# layout.net
KiCad netlist of a schematic drawn in EAGLE
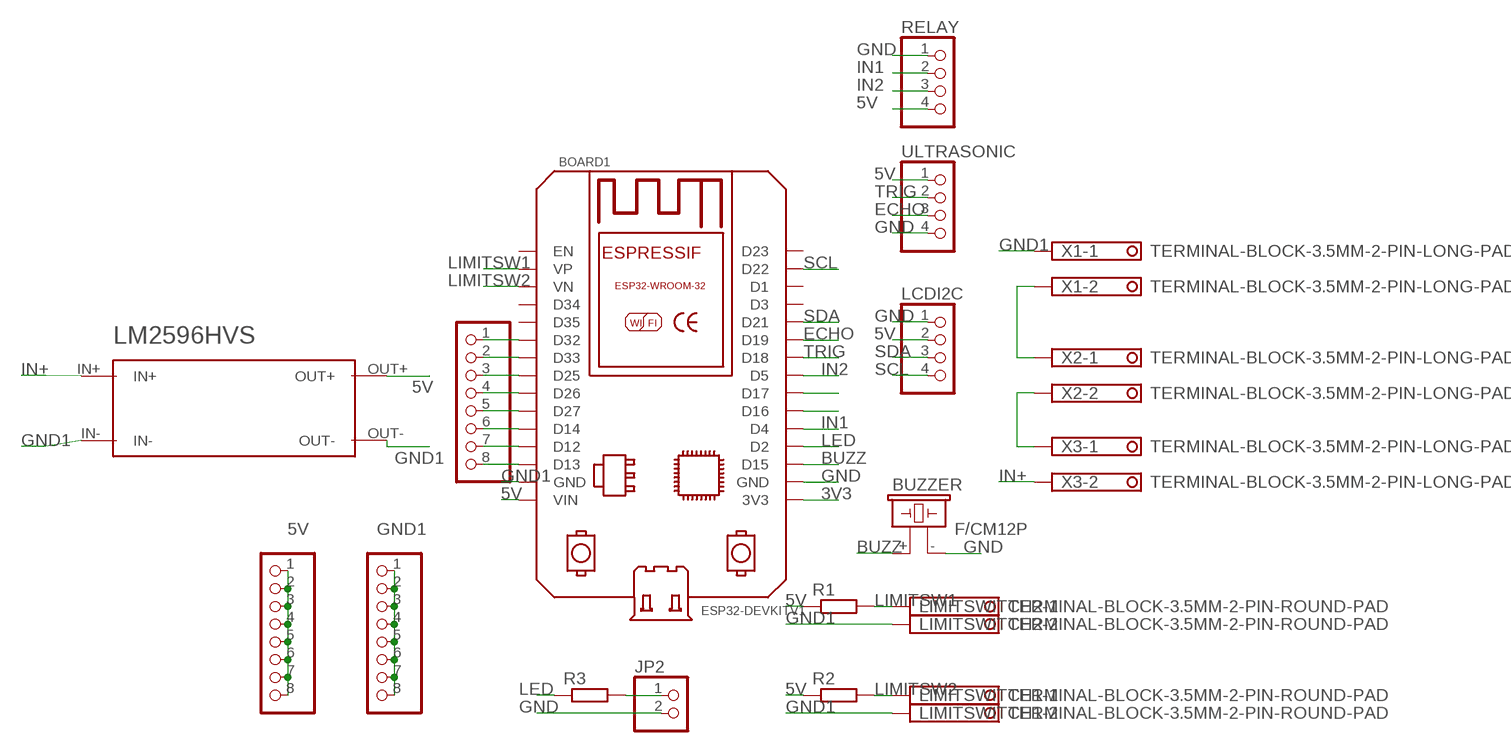
[diagram p0: schematic, sheet 1]

(export (version "E")
  (design (tool "Eeschema 10.0.6"))
  (components
    (comp (ref "BOARD1")
      (value "ESP32DEVKITV1SHRIDATTDUDHAT")
      (footprint "eagle-import:ESP32-DEVKITV1")
      (libsource (lib "eagle-import") (part "ESP32DEVKITV1SHRIDATTDUDHAT"))
    )
    (comp (ref "BUZZER")
      (value "F/CM12P")
      (footprint "eagle-import:F_CM12P")
      (libsource (lib "eagle-import") (part "F/CM12P"))
    )
    (comp (ref "JP1")
      (value "PINHD-1X8")
      (footprint "eagle-import:1X08")
      (libsource (lib "eagle-import") (part "PINHD-1X8"))
    )
    (comp (ref "JP2")
      (value "PINHD-1X2")
      (footprint "eagle-import:1X02")
      (libsource (lib "eagle-import") (part "PINHD-1X2"))
    )
    (comp (ref "JP3")
      (value "PINHD-1X8")
      (footprint "eagle-import:1X08")
      (libsource (lib "eagle-import") (part "PINHD-1X8"))
    )
    (comp (ref "JP4")
      (value "PINHD-1X8")
      (footprint "eagle-import:1X08")
      (libsource (lib "eagle-import") (part "PINHD-1X8"))
    )
    (comp (ref "LCDI2C")
      (value "PINHD-1X4")
      (footprint "eagle-import:1X04")
      (libsource (lib "eagle-import") (part "PINHD-1X4"))
    )
    (comp (ref "LIMITSWITCH1")
      (value "TERMINAL-BLOCK-3.5MM-2-PIN-ROUND-PAD")
      (footprint "eagle-import:TERMINAL-BLOCK-2-PIN-3.5MM-ROUND-PAD")
      (libsource (lib "eagle-import") (part "TERMINAL-BLOCK-3.5MM-2-PIN-ROUND-PAD"))
    )
    (comp (ref "LIMITSWITCH2")
      (value "TERMINAL-BLOCK-3.5MM-2-PIN-ROUND-PAD")
      (footprint "eagle-import:TERMINAL-BLOCK-2-PIN-3.5MM-ROUND-PAD")
      (libsource (lib "eagle-import") (part "TERMINAL-BLOCK-3.5MM-2-PIN-ROUND-PAD"))
    )
    (comp (ref "R1")
      (value "R-EU_0207/10")
      (footprint "eagle-import:0207_10")
      (libsource (lib "eagle-import") (part "R-EU_0207/10"))
    )
    (comp (ref "R2")
      (value "R-EU_0207/10")
      (footprint "eagle-import:0207_10")
      (libsource (lib "eagle-import") (part "R-EU_0207/10"))
    )
    (comp (ref "R3")
      (value "R-EU_0207/10")
      (footprint "eagle-import:0207_10")
      (libsource (lib "eagle-import") (part "R-EU_0207/10"))
    )
    (comp (ref "RELAY")
      (value "PINHD-1X4")
      (footprint "eagle-import:1X04")
      (libsource (lib "eagle-import") (part "PINHD-1X4"))
    )
    (comp (ref "STEP_DOWN1")
      (value "LM2596HVS")
      (footprint "eagle-import:LM2596HVS")
      (libsource (lib "eagle-import") (part "LM2596HVS"))
    )
    (comp (ref "ULTRASONIC")
      (value "PINHD-1X4")
      (footprint "eagle-import:1X04")
      (libsource (lib "eagle-import") (part "PINHD-1X4"))
    )
    (comp (ref "X1")
      (value "TERMINAL-BLOCK-3.5MM-2-PIN-LONG-PAD")
      (footprint "eagle-import:TERMINAL-BLOCK-2-PIN-3.5MM-LONG-PAD")
      (libsource (lib "eagle-import") (part "TERMINAL-BLOCK-3.5MM-2-PIN-LONG-PAD"))
    )
    (comp (ref "X2")
      (value "TERMINAL-BLOCK-3.5MM-2-PIN-LONG-PAD")
      (footprint "eagle-import:TERMINAL-BLOCK-2-PIN-3.5MM-LONG-PAD")
      (libsource (lib "eagle-import") (part "TERMINAL-BLOCK-3.5MM-2-PIN-LONG-PAD"))
    )
    (comp (ref "X3")
      (value "TERMINAL-BLOCK-3.5MM-2-PIN-LONG-PAD")
      (footprint "eagle-import:TERMINAL-BLOCK-2-PIN-3.5MM-LONG-PAD")
      (libsource (lib "eagle-import") (part "TERMINAL-BLOCK-3.5MM-2-PIN-LONG-PAD"))
    )
  )
  (nets
    (net (code "1") (name "/3V3") (class "Default")
      (node (ref "BOARD1") (pin "3V3") (pinfunction "3V3_3V3") (pintype "bidirectional"))
    )
    (net (code "2") (name "/5V") (class "Default")
      (node (ref "BOARD1") (pin "VIN") (pinfunction "VIN_VIN") (pintype "bidirectional"))
      (node (ref "JP3") (pin "1") (pinfunction "1_1") (pintype "passive"))
      (node (ref "JP3") (pin "2") (pinfunction "2_2") (pintype "passive"))
      (node (ref "JP3") (pin "3") (pinfunction "3_3") (pintype "passive"))
      (node (ref "JP3") (pin "4") (pinfunction "4_4") (pintype "passive"))
      (node (ref "JP3") (pin "5") (pinfunction "5_5") (pintype "passive"))
      (node (ref "JP3") (pin "6") (pinfunction "6_6") (pintype "passive"))
      (node (ref "JP3") (pin "7") (pinfunction "7_7") (pintype "passive"))
      (node (ref "JP3") (pin "8") (pinfunction "8_8") (pintype "passive"))
      (node (ref "LCDI2C") (pin "2") (pinfunction "2_2") (pintype "passive"))
      (node (ref "R1") (pin "1") (pinfunction "1_1") (pintype "passive"))
      (node (ref "R2") (pin "1") (pinfunction "1_1") (pintype "passive"))
      (node (ref "RELAY") (pin "4") (pinfunction "4_4") (pintype "passive"))
      (node (ref "STEP_DOWN1") (pin "OUT+") (pinfunction "OUT+_OUT+") (pintype "bidirectional"))
      (node (ref "ULTRASONIC") (pin "1") (pinfunction "1_1") (pintype "passive"))
    )
    (net (code "3") (name "/BUZZ") (class "Default")
      (node (ref "BOARD1") (pin "D15") (pinfunction "D15_D15") (pintype "bidirectional"))
      (node (ref "BUZZER") (pin "+") (pinfunction "1_+") (pintype "passive"))
    )
    (net (code "4") (name "/ECHO") (class "Default")
      (node (ref "BOARD1") (pin "D19") (pinfunction "D19_D19") (pintype "bidirectional"))
      (node (ref "ULTRASONIC") (pin "3") (pinfunction "3_3") (pintype "passive"))
    )
    (net (code "5") (name "/GND") (class "Default")
      (node (ref "BOARD1") (pin "GND@1") (pinfunction "GND_GND@1") (pintype "bidirectional"))
      (node (ref "BUZZER") (pin "-") (pinfunction "2_-") (pintype "passive"))
      (node (ref "JP2") (pin "2") (pinfunction "2_2") (pintype "passive"))
      (node (ref "LCDI2C") (pin "1") (pinfunction "1_1") (pintype "passive"))
      (node (ref "RELAY") (pin "1") (pinfunction "1_1") (pintype "passive"))
      (node (ref "ULTRASONIC") (pin "4") (pinfunction "4_4") (pintype "passive"))
    )
    (net (code "6") (name "/GND1") (class "Default")
      (node (ref "BOARD1") (pin "GND") (pinfunction "GND_GND") (pintype "bidirectional"))
      (node (ref "JP4") (pin "1") (pinfunction "1_1") (pintype "passive"))
      (node (ref "JP4") (pin "2") (pinfunction "2_2") (pintype "passive"))
      (node (ref "JP4") (pin "3") (pinfunction "3_3") (pintype "passive"))
      (node (ref "JP4") (pin "4") (pinfunction "4_4") (pintype "passive"))
      (node (ref "JP4") (pin "5") (pinfunction "5_5") (pintype "passive"))
      (node (ref "JP4") (pin "6") (pinfunction "6_6") (pintype "passive"))
      (node (ref "JP4") (pin "7") (pinfunction "7_7") (pintype "passive"))
      (node (ref "JP4") (pin "8") (pinfunction "8_8") (pintype "passive"))
      (node (ref "LIMITSWITCH1") (pin "2") (pinfunction "K_2") (pintype "passive"))
      (node (ref "LIMITSWITCH2") (pin "2") (pinfunction "K_2") (pintype "passive"))
      (node (ref "STEP_DOWN1") (pin "IN-") (pinfunction "IN-_IN-") (pintype "bidirectional"))
      (node (ref "STEP_DOWN1") (pin "OUT-") (pinfunction "OUT-_OUT-") (pintype "bidirectional"))
      (node (ref "X1") (pin "1") (pinfunction "K_1") (pintype "passive"))
    )
    (net (code "7") (name "/IN+") (class "Default")
      (node (ref "STEP_DOWN1") (pin "IN+") (pinfunction "IN+_IN+") (pintype "bidirectional"))
      (node (ref "X3") (pin "2") (pinfunction "K_2") (pintype "passive"))
    )
    (net (code "8") (name "/IN1") (class "Default")
      (node (ref "BOARD1") (pin "D4") (pinfunction "D4_D4") (pintype "bidirectional"))
      (node (ref "RELAY") (pin "2") (pinfunction "2_2") (pintype "passive"))
    )
    (net (code "9") (name "/IN2") (class "Default")
      (node (ref "BOARD1") (pin "D5") (pinfunction "D5_D5") (pintype "bidirectional"))
      (node (ref "RELAY") (pin "3") (pinfunction "3_3") (pintype "passive"))
    )
    (net (code "10") (name "/LED") (class "Default")
      (node (ref "BOARD1") (pin "D2") (pinfunction "D2_D2") (pintype "bidirectional"))
      (node (ref "R3") (pin "1") (pinfunction "1_1") (pintype "passive"))
    )
    (net (code "11") (name "/LIMITSW1") (class "Default")
      (node (ref "BOARD1") (pin "VP") (pinfunction "VP_VP") (pintype "bidirectional"))
      (node (ref "LIMITSWITCH2") (pin "1") (pinfunction "K_1") (pintype "passive"))
      (node (ref "R1") (pin "2") (pinfunction "2_2") (pintype "passive"))
    )
    (net (code "12") (name "/LIMITSW2") (class "Default")
      (node (ref "BOARD1") (pin "VN") (pinfunction "VN_VN") (pintype "bidirectional"))
      (node (ref "LIMITSWITCH1") (pin "1") (pinfunction "K_1") (pintype "passive"))
      (node (ref "R2") (pin "2") (pinfunction "2_2") (pintype "passive"))
    )
    (net (code "13") (name "/SCL") (class "Default")
      (node (ref "BOARD1") (pin "D22") (pinfunction "D22_D22") (pintype "bidirectional"))
      (node (ref "LCDI2C") (pin "4") (pinfunction "4_4") (pintype "passive"))
    )
    (net (code "14") (name "/SDA") (class "Default")
      (node (ref "BOARD1") (pin "D21") (pinfunction "D21_D21") (pintype "bidirectional"))
      (node (ref "LCDI2C") (pin "3") (pinfunction "3_3") (pintype "passive"))
    )
    (net (code "15") (name "/TRIG") (class "Default")
      (node (ref "BOARD1") (pin "D18") (pinfunction "D18_D18") (pintype "bidirectional"))
      (node (ref "ULTRASONIC") (pin "2") (pinfunction "2_2") (pintype "passive"))
    )
    (net (code "16") (name "Net-(BOARD1-PadD12)") (class "Default")
      (node (ref "BOARD1") (pin "D12") (pinfunction "D12_D12") (pintype "bidirectional"))
      (node (ref "JP1") (pin "7") (pinfunction "7_7") (pintype "passive"))
    )
    (net (code "17") (name "Net-(BOARD1-PadD13)") (class "Default")
      (node (ref "BOARD1") (pin "D13") (pinfunction "D13_D13") (pintype "bidirectional"))
      (node (ref "JP1") (pin "8") (pinfunction "8_8") (pintype "passive"))
    )
    (net (code "18") (name "Net-(BOARD1-PadD14)") (class "Default")
      (node (ref "BOARD1") (pin "D14") (pinfunction "D14_D14") (pintype "bidirectional"))
      (node (ref "JP1") (pin "6") (pinfunction "6_6") (pintype "passive"))
    )
    (net (code "19") (name "Net-(BOARD1-PadD25)") (class "Default")
      (node (ref "BOARD1") (pin "D25") (pinfunction "D25_D25") (pintype "bidirectional"))
      (node (ref "JP1") (pin "3") (pinfunction "3_3") (pintype "passive"))
    )
    (net (code "20") (name "Net-(BOARD1-PadD26)") (class "Default")
      (node (ref "BOARD1") (pin "D26") (pinfunction "D26_D26") (pintype "bidirectional"))
      (node (ref "JP1") (pin "4") (pinfunction "4_4") (pintype "passive"))
    )
    (net (code "21") (name "Net-(BOARD1-PadD27)") (class "Default")
      (node (ref "BOARD1") (pin "D27") (pinfunction "D27_D27") (pintype "bidirectional"))
      (node (ref "JP1") (pin "5") (pinfunction "5_5") (pintype "passive"))
    )
    (net (code "22") (name "Net-(BOARD1-PadD32)") (class "Default")
      (node (ref "BOARD1") (pin "D32") (pinfunction "D32_D32") (pintype "bidirectional"))
      (node (ref "JP1") (pin "1") (pinfunction "1_1") (pintype "passive"))
    )
    (net (code "23") (name "Net-(BOARD1-PadD33)") (class "Default")
      (node (ref "BOARD1") (pin "D33") (pinfunction "D33_D33") (pintype "bidirectional"))
      (node (ref "JP1") (pin "2") (pinfunction "2_2") (pintype "passive"))
    )
    (net (code "24") (name "Net-(JP2-Pad1)") (class "Default")
      (node (ref "JP2") (pin "1") (pinfunction "1_1") (pintype "passive"))
      (node (ref "R3") (pin "2") (pinfunction "2_2") (pintype "passive"))
    )
    (net (code "25") (name "Net-(X1B-K)") (class "Default")
      (node (ref "X1") (pin "2") (pinfunction "K_2") (pintype "passive"))
      (node (ref "X2") (pin "1") (pinfunction "K_1") (pintype "passive"))
    )
    (net (code "26") (name "Net-(X2B-K)") (class "Default")
      (node (ref "X2") (pin "2") (pinfunction "K_2") (pintype "passive"))
      (node (ref "X3") (pin "1") (pinfunction "K_1") (pintype "passive"))
    )
    (net (code "27") (name "unconnected-(BOARD1-PadD1)") (class "Default")
      (node (ref "BOARD1") (pin "D1") (pinfunction "D1_D1") (pintype "bidirectional"))
    )
    (net (code "28") (name "unconnected-(BOARD1-PadD3)") (class "Default")
      (node (ref "BOARD1") (pin "D3") (pinfunction "D3_D3") (pintype "bidirectional"))
    )
    (net (code "29") (name "unconnected-(BOARD1-PadD16)") (class "Default")
      (node (ref "BOARD1") (pin "D16") (pinfunction "D16_D16") (pintype "bidirectional"))
    )
    (net (code "30") (name "unconnected-(BOARD1-PadD17)") (class "Default")
      (node (ref "BOARD1") (pin "D17") (pinfunction "D17_D17") (pintype "bidirectional"))
    )
    (net (code "31") (name "unconnected-(BOARD1-PadD23)") (class "Default")
      (node (ref "BOARD1") (pin "D23") (pinfunction "D23_D23") (pintype "bidirectional"))
    )
    (net (code "32") (name "unconnected-(BOARD1-PadD34)") (class "Default")
      (node (ref "BOARD1") (pin "D34") (pinfunction "D34_D34") (pintype "bidirectional"))
    )
    (net (code "33") (name "unconnected-(BOARD1-PadD35)") (class "Default")
      (node (ref "BOARD1") (pin "D35") (pinfunction "D35_D35") (pintype "bidirectional"))
    )
    (net (code "34") (name "unconnected-(BOARD1-PadEN)") (class "Default")
      (node (ref "BOARD1") (pin "EN") (pinfunction "EN_EN") (pintype "bidirectional"))
    )
  )
)
